# SectionB_Schematic.net
KiCad netlist of a schematic drawn in EAGLE
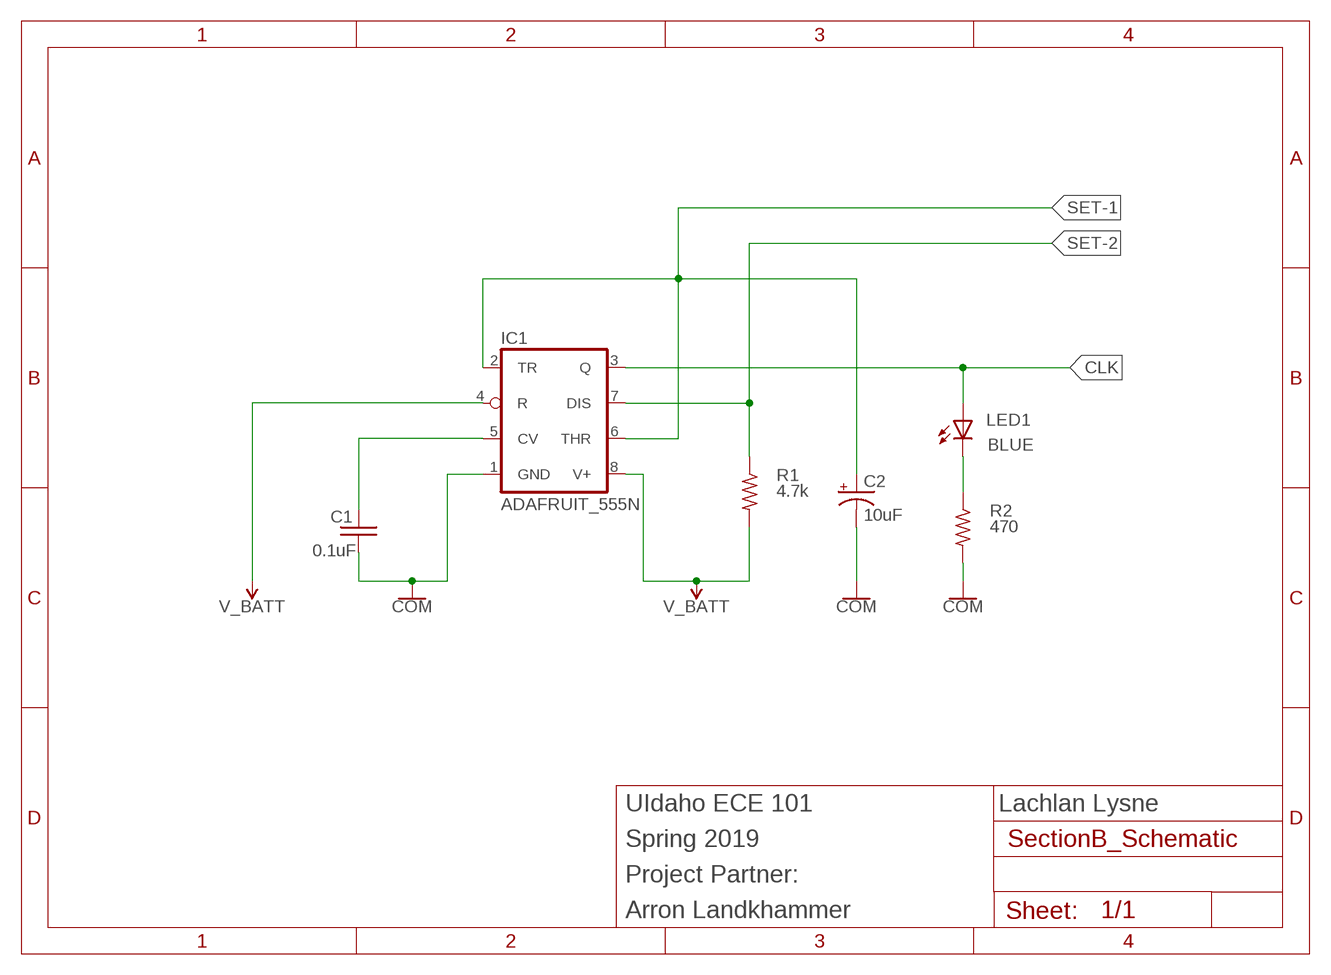
[diagram p0: schematic, sheet 1]

(export (version "E")
  (design (tool "Eeschema 10.0.6"))
  (components
    (comp (ref "C1")
      (value "0.1uF")
      (footprint "eagle-import:ADAFRUIT_C025-025X050")
      (libsource (lib "eagle-import") (part "ADAFRUIT_C-US025-025X050"))
    )
    (comp (ref "C2")
      (value "10uF")
      (footprint "eagle-import:ADAFRUIT_E2-5")
      (libsource (lib "eagle-import") (part "ADAFRUIT_CPOL-USE2-5"))
    )
    (comp (ref "IC1")
      (value "ADAFRUIT_555N")
      (footprint "eagle-import:ADAFRUIT_DIL08-ROUND")
      (libsource (lib "eagle-import") (part "ADAFRUIT_555N"))
    )
    (comp (ref "LED1")
      (value "ADAFRUIT_LED5MM")
      (footprint "eagle-import:ADAFRUIT_LED5MM")
      (fields (field (name "COLOR") "BLUE"))
      (libsource (lib "eagle-import") (part "ADAFRUIT_LED5MM"))
    )
    (comp (ref "R1")
      (value "4.7k")
      (footprint "eagle-import:ADAFRUIT_0207_10")
      (libsource (lib "eagle-import") (part "ADAFRUIT_R-US_0207/10"))
    )
    (comp (ref "R2")
      (value "470")
      (footprint "eagle-import:ADAFRUIT_0207_10")
      (libsource (lib "eagle-import") (part "ADAFRUIT_R-US_0207/10"))
    )
  )
  (nets
    (net (code "1") (name "CLK") (class "Default")
      (node (ref "IC1") (pin "3") (pinfunction "Q_3") (pintype "output"))
      (node (ref "LED1") (pin "A") (pinfunction "A_A") (pintype "passive"))
    )
    (net (code "2") (name "COM") (class "Default")
      (node (ref "C1") (pin "2") (pinfunction "2_2") (pintype "passive"))
      (node (ref "C2") (pin "-") (pinfunction "-_-") (pintype "passive"))
      (node (ref "IC1") (pin "1") (pinfunction "GND_1") (pintype "power_in"))
      (node (ref "R2") (pin "2") (pinfunction "2_2") (pintype "passive"))
    )
    (net (code "3") (name "Net-(IC1-CV)") (class "Default")
      (node (ref "C1") (pin "1") (pinfunction "1_1") (pintype "passive"))
      (node (ref "IC1") (pin "5") (pinfunction "CV_5") (pintype "input"))
    )
    (net (code "4") (name "Net-(LED1-C)") (class "Default")
      (node (ref "LED1") (pin "K") (pinfunction "C_K") (pintype "passive"))
      (node (ref "R2") (pin "1") (pinfunction "1_1") (pintype "passive"))
    )
    (net (code "5") (name "SET-1") (class "Default")
      (node (ref "C2") (pin "+") (pinfunction "+_+") (pintype "passive"))
      (node (ref "IC1") (pin "2") (pinfunction "TR_2") (pintype "input"))
      (node (ref "IC1") (pin "6") (pinfunction "THR_6") (pintype "input"))
    )
    (net (code "6") (name "SET-2") (class "Default")
      (node (ref "IC1") (pin "7") (pinfunction "DIS_7") (pintype "input"))
      (node (ref "R1") (pin "1") (pinfunction "1_1") (pintype "passive"))
    )
    (net (code "7") (name "V_BATT") (class "Default")
      (node (ref "IC1") (pin "4") (pinfunction "R_4") (pintype "input"))
      (node (ref "IC1") (pin "8") (pinfunction "V+_8") (pintype "power_in"))
      (node (ref "R1") (pin "2") (pinfunction "2_2") (pintype "passive"))
    )
  )
)
